# PowerSupply.net
KiCad netlist of a schematic drawn in Altium Designer
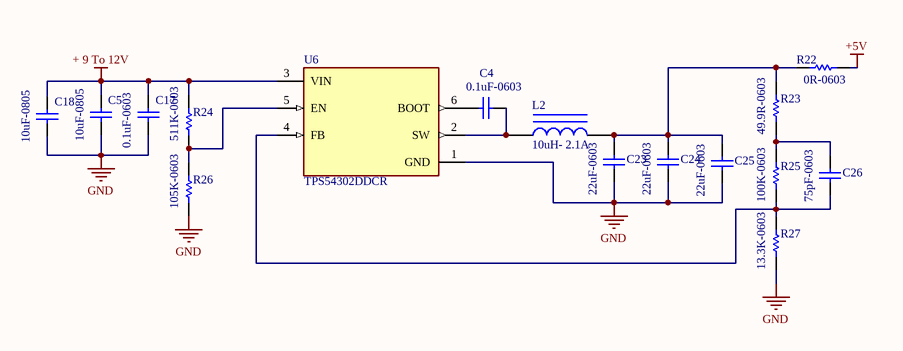
[diagram p0: PowerSupply.SchDoc]

(export (version "E")
  (design (tool "Eeschema 10.0.6"))
  (components
    (comp (ref "C4")
      (value "0.1uF-0603")
      (footprint "C0603")
      (description "CAP CER 0.47UF 50V X7R 0603")
      (fields (field (name "MANUFACTURER PART NUMBER") "CC0603KRX7R9BB104"))
      (libsource (lib "Ravi") (part "Capacitor_Ceramic"))
    )
    (comp (ref "C5")
      (value "10uF-0805")
      (footprint "C0805")
      (description "CAP CER 0.47UF 50V X7R 0603")
      (fields (field (name "MANUFACTURER PART NUMBER") "CL21A106KAYNNNE"))
      (libsource (lib "Ravi") (part "Capacitor_Ceramic"))
    )
    (comp (ref "C17")
      (value "0.1uF-0603")
      (footprint "C0603")
      (description "CAP CER 0.1UF 50V X7R 0603")
      (fields (field (name "MANUFACTURER PART NUMBER") "CC0603KRX7R9BB104"))
      (libsource (lib "Ravi") (part "Capacitor_Ceramic"))
    )
    (comp (ref "C18")
      (value "10uF-0805")
      (footprint "C0805")
      (description "CAP CER 0.47UF 50V X7R 0603")
      (fields (field (name "MANUFACTURER PART NUMBER") "CL21A106KAYNNNE"))
      (libsource (lib "Ravi") (part "Capacitor_Ceramic"))
    )
    (comp (ref "C23")
      (value "22uF-0603")
      (footprint "C0603")
      (description "CAP CER 22UF 10V X7R 0603")
      (fields (field (name "MANUFACTURER PART NUMBER") "CL10A226MP8NUNE"))
      (libsource (lib "Ravi") (part "Capacitor_Ceramic"))
    )
    (comp (ref "C24")
      (value "22uF-0603")
      (footprint "C0603")
      (description "CAP CER 22UF 10V X7R 0603")
      (fields (field (name "MANUFACTURER PART NUMBER") "CL10A226MP8NUNE"))
      (libsource (lib "Ravi") (part "Capacitor_Ceramic"))
    )
    (comp (ref "C25")
      (value "22uF-0603")
      (footprint "C0603")
      (description "CAP CER 22UF 10V X7R 0603")
      (fields (field (name "MANUFACTURER PART NUMBER") "CL10A226MP8NUNE"))
      (libsource (lib "Ravi") (part "Capacitor_Ceramic"))
    )
    (comp (ref "C26")
      (value "75pF-0603")
      (footprint "C0603")
      (description "CAP CER 22UF 10V X7R 0603")
      (fields (field (name "MANUFACTURER PART NUMBER") "CC0603JRNPO9BN750"))
      (libsource (lib "Ravi") (part "Capacitor_Ceramic"))
    )
    (comp (ref "L2")
      (value "10uH- 2.1A")
      (footprint "FERRITE_COIL_XFL4020_0")
      (description "Power Inductors 2.1A 10uH ±20% 30mΩ SMD,4x4x3mm")
      (fields (field (name "MANUFACTURER PART NUMBER") "SWPA4030S100MT"))
      (libsource (lib "Ravi") (part "Ferrite_Coil"))
    )
    (comp (ref "R22")
      (value "0R-0603")
      (footprint "R0603")
      (description "RES 0 OHM 1% 1/8W 0603")
      (fields (field (name "MANUFACTURER PART NUMBER") "RMCF0603ZT0R00"))
      (libsource (lib "uINVERTER") (part "RES_3.3k_0603"))
    )
    (comp (ref "R23")
      (value "49.9R-0603")
      (footprint "R0603")
      (description "RES 49.9 OHM 1% 1/10W 0603")
      (fields (field (name "MANUFACTURER PART NUMBER") "RC0603FR-0749R9L"))
      (libsource (lib "uINVERTER") (part "RES_3.3k_0603"))
    )
    (comp (ref "R24")
      (value "511K-0603")
      (footprint "R0603")
      (description "RES 511K OHM 1% 1/10W 0603")
      (fields (field (name "MANUFACTURER PART NUMBER") "AC0603FR-07511KL"))
      (libsource (lib "uINVERTER") (part "RES_3.3k_0603"))
    )
    (comp (ref "R25")
      (value "100K-0603")
      (footprint "R0603")
      (description "RES 100K OHM 1% 1/10W 0603")
      (fields (field (name "MANUFACTURER PART NUMBER") "RC0603JR-07100KL"))
      (libsource (lib "uINVERTER") (part "RES_3.3k_0603"))
    )
    (comp (ref "R26")
      (value "105K-0603")
      (footprint "R0603")
      (description "RES 105K OHM 1% 1/10W 0603")
      (fields (field (name "MANUFACTURER PART NUMBER") "RC0603FR-07105KL"))
      (libsource (lib "uINVERTER") (part "RES_3.3k_0603"))
    )
    (comp (ref "R27")
      (value "13.3K-0603")
      (footprint "R0603")
      (description "RES 13.3K OHM 1% 1/10W 0603")
      (fields (field (name "MANUFACTURER PART NUMBER") "RC0603FR-0713K3L"))
      (libsource (lib "uINVERTER") (part "RES_3.3k_0603"))
    )
    (comp (ref "U6")
      (value "TPS54302DDCR")
      (footprint "SOT95P280X110-6N")
      (libsource (lib "Ravi") (part "TPS54X02DDCR"))
    )
  )
  (nets
    (net (code "1") (name "+ 9 To 12V") (class "Default")
      (node (ref "C17") (pin "2") (pinfunction "2_2") (pintype "passive"))
      (node (ref "C18") (pin "2") (pinfunction "2_2") (pintype "passive"))
      (node (ref "C5") (pin "2") (pinfunction "2_2") (pintype "passive"))
      (node (ref "R24") (pin "2") (pinfunction "2_2") (pintype "passive"))
      (node (ref "U6") (pin "3") (pinfunction "VIN_3") (pintype "power_in"))
    )
    (net (code "2") (name "+5V") (class "Default")
      (node (ref "R22") (pin "2") (pinfunction "2_2") (pintype "passive"))
    )
    (net (code "3") (name "GND") (class "Default")
      (node (ref "C17") (pin "1") (pinfunction "1_1") (pintype "passive"))
      (node (ref "C18") (pin "1") (pinfunction "1_1") (pintype "passive"))
      (node (ref "C23") (pin "2") (pinfunction "2_2") (pintype "passive"))
      (node (ref "C24") (pin "2") (pinfunction "2_2") (pintype "passive"))
      (node (ref "C25") (pin "2") (pinfunction "2_2") (pintype "passive"))
      (node (ref "C5") (pin "1") (pinfunction "1_1") (pintype "passive"))
      (node (ref "R26") (pin "1") (pinfunction "1_1") (pintype "passive"))
      (node (ref "R27") (pin "1") (pinfunction "1_1") (pintype "passive"))
      (node (ref "U6") (pin "1") (pinfunction "GND_1") (pintype "power_in"))
    )
    (net (code "4") (name "Net-(C23-Pad1)") (class "Default")
      (node (ref "C23") (pin "1") (pinfunction "1_1") (pintype "passive"))
      (node (ref "C24") (pin "1") (pinfunction "1_1") (pintype "passive"))
      (node (ref "C25") (pin "1") (pinfunction "1_1") (pintype "passive"))
      (node (ref "L2") (pin "2") (pinfunction "2_2") (pintype "passive"))
      (node (ref "R22") (pin "1") (pinfunction "1_1") (pintype "passive"))
      (node (ref "R23") (pin "2") (pinfunction "2_2") (pintype "passive"))
    )
    (net (code "5") (name "Net-(C26-Pad1)") (class "Default")
      (node (ref "C26") (pin "1") (pinfunction "1_1") (pintype "passive"))
      (node (ref "R23") (pin "1") (pinfunction "1_1") (pintype "passive"))
      (node (ref "R25") (pin "2") (pinfunction "2_2") (pintype "passive"))
    )
    (net (code "6") (name "Net-(U6-BOOT)") (class "Default")
      (node (ref "C4") (pin "2") (pinfunction "2_2") (pintype "passive"))
      (node (ref "U6") (pin "6") (pinfunction "BOOT_6") (pintype "output"))
    )
    (net (code "7") (name "Net-(U6-EN)") (class "Default")
      (node (ref "R24") (pin "1") (pinfunction "1_1") (pintype "passive"))
      (node (ref "R26") (pin "2") (pinfunction "2_2") (pintype "passive"))
      (node (ref "U6") (pin "5") (pinfunction "EN_5") (pintype "input"))
    )
    (net (code "8") (name "Net-(U6-FB)") (class "Default")
      (node (ref "C26") (pin "2") (pinfunction "2_2") (pintype "passive"))
      (node (ref "R25") (pin "1") (pinfunction "1_1") (pintype "passive"))
      (node (ref "R27") (pin "2") (pinfunction "2_2") (pintype "passive"))
      (node (ref "U6") (pin "4") (pinfunction "FB_4") (pintype "input"))
    )
    (net (code "9") (name "Net-(U6-SW)") (class "Default")
      (node (ref "C4") (pin "1") (pinfunction "1_1") (pintype "passive"))
      (node (ref "L2") (pin "1") (pinfunction "1_1") (pintype "passive"))
      (node (ref "U6") (pin "2") (pinfunction "SW_2") (pintype "output"))
    )
  )
)
